# Connectors.net
KiCad netlist of a schematic drawn in Altium Designer
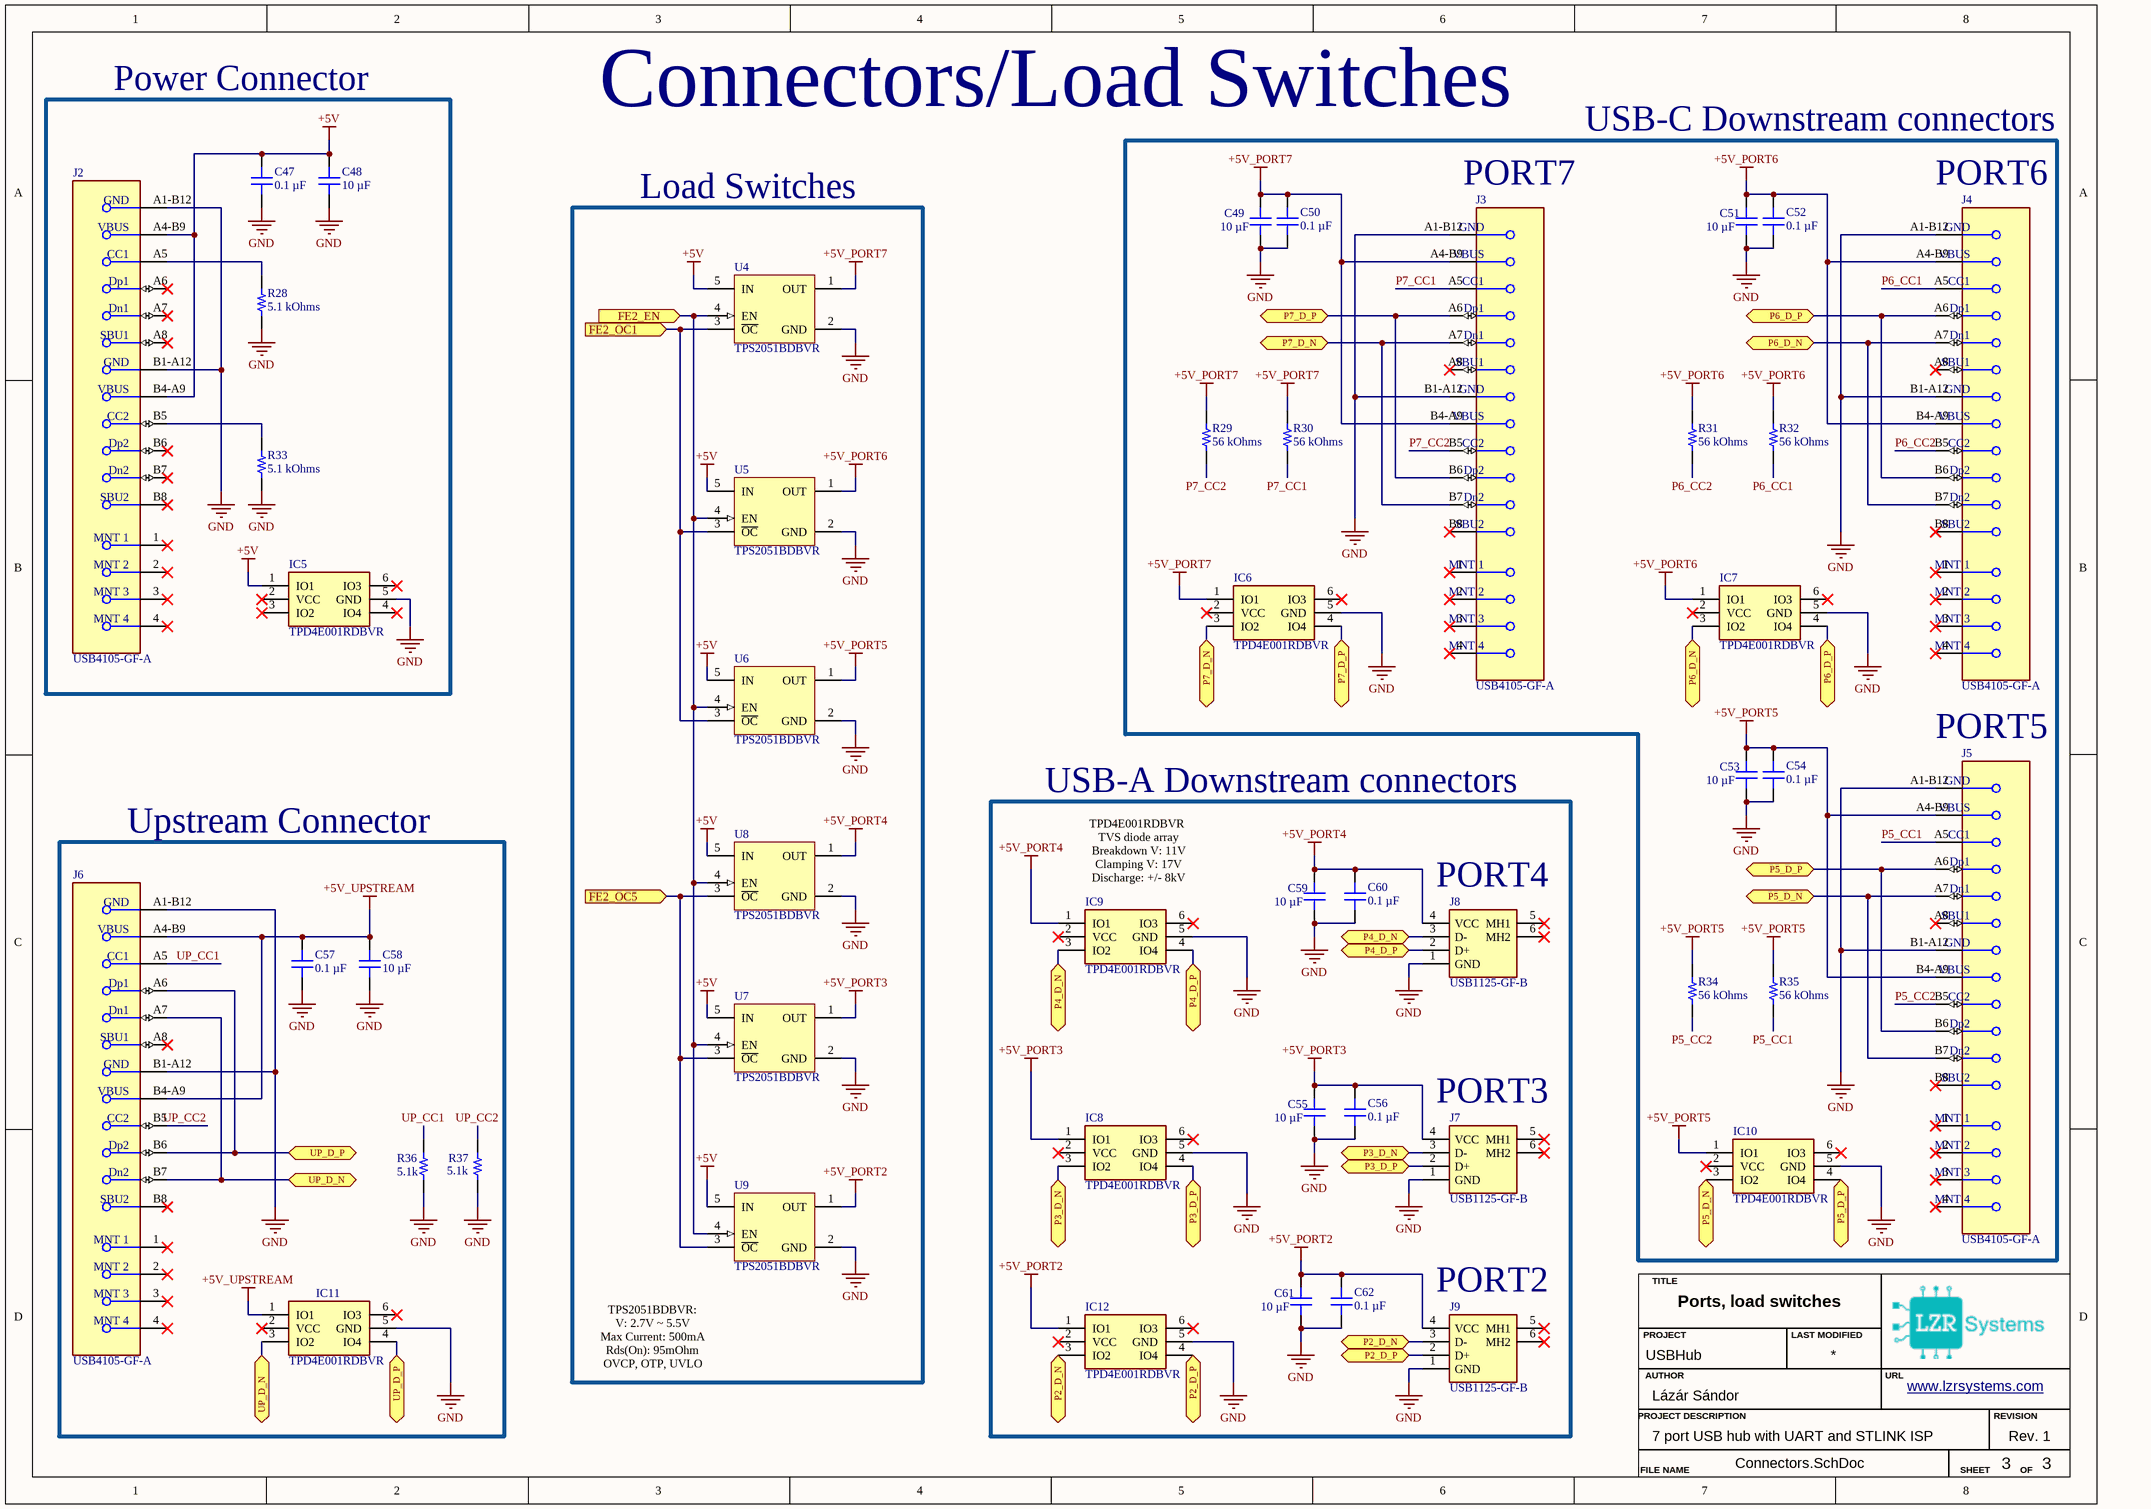
[diagram p0: Connectors.SchDoc]

(export (version "E")
  (design (tool "Eeschema 10.0.6"))
  (components
    (comp (ref "C47")
      (value "0.1 µF")
      (footprint "CAP 0603_1608")
      (description "CAP CER 0.1UF 50V X7R 0603")
      (fields
        (field (name "PART NUMBER") "GCJ188R71H104KA12D")
        (field (name "CAPACITANCE") "0.1 µF")
        (field (name "MANUFACTURER") "Murata Electronics")
      )
      (libsource (lib "Celestial Altium Library - altium_library") (part "Capacitor"))
    )
    (comp (ref "C48")
      (value "10 µF")
      (footprint "MURATA GRM21B 0805_2012")
      (description "CAP CER 10UF 25V X5R 0805")
      (fields
        (field (name "PART NUMBER") "GRM21BR61E106KA73K")
        (field (name "CAPACITANCE") "10 µF")
        (field (name "MANUFACTURER") "Murata Electronics")
      )
      (libsource (lib "Celestial Altium Library - altium_library") (part "Capacitor"))
    )
    (comp (ref "C49")
      (value "10 µF")
      (footprint "MURATA GRM21B 0805_2012")
      (description "CAP CER 10UF 25V X5R 0805")
      (fields
        (field (name "PART NUMBER") "GRM21BR61E106KA73K")
        (field (name "CAPACITANCE") "10 µF")
        (field (name "MANUFACTURER") "Murata Electronics")
      )
      (libsource (lib "Celestial Altium Library - altium_library") (part "Capacitor"))
    )
    (comp (ref "C50")
      (value "0.1 µF")
      (footprint "CAP 0603_1608")
      (description "CAP CER 0.1UF 50V X7R 0603")
      (fields
        (field (name "PART NUMBER") "GCJ188R71H104KA12D")
        (field (name "CAPACITANCE") "0.1 µF")
        (field (name "MANUFACTURER") "Murata Electronics")
      )
      (libsource (lib "Celestial Altium Library - altium_library") (part "Capacitor"))
    )
    (comp (ref "C51")
      (value "10 µF")
      (footprint "MURATA GRM21B 0805_2012")
      (description "CAP CER 10UF 25V X5R 0805")
      (fields
        (field (name "PART NUMBER") "GRM21BR61E106KA73K")
        (field (name "CAPACITANCE") "10 µF")
        (field (name "MANUFACTURER") "Murata Electronics")
      )
      (libsource (lib "Celestial Altium Library - altium_library") (part "Capacitor"))
    )
    (comp (ref "C52")
      (value "0.1 µF")
      (footprint "CAP 0603_1608")
      (description "CAP CER 0.1UF 50V X7R 0603")
      (fields
        (field (name "PART NUMBER") "GCJ188R71H104KA12D")
        (field (name "CAPACITANCE") "0.1 µF")
        (field (name "MANUFACTURER") "Murata Electronics")
      )
      (libsource (lib "Celestial Altium Library - altium_library") (part "Capacitor"))
    )
    (comp (ref "C53")
      (value "10 µF")
      (footprint "MURATA GRM21B 0805_2012")
      (description "CAP CER 10UF 25V X5R 0805")
      (fields
        (field (name "PART NUMBER") "GRM21BR61E106KA73K")
        (field (name "CAPACITANCE") "10 µF")
        (field (name "MANUFACTURER") "Murata Electronics")
      )
      (libsource (lib "Celestial Altium Library - altium_library") (part "Capacitor"))
    )
    (comp (ref "C54")
      (value "0.1 µF")
      (footprint "CAP 0603_1608")
      (description "CAP CER 0.1UF 50V X7R 0603")
      (fields
        (field (name "PART NUMBER") "GCJ188R71H104KA12D")
        (field (name "CAPACITANCE") "0.1 µF")
        (field (name "MANUFACTURER") "Murata Electronics")
      )
      (libsource (lib "Celestial Altium Library - altium_library") (part "Capacitor"))
    )
    (comp (ref "C55")
      (value "10 µF")
      (footprint "MURATA GRM21B 0805_2012")
      (description "CAP CER 10UF 25V X5R 0805")
      (fields
        (field (name "PART NUMBER") "GRM21BR61E106KA73K")
        (field (name "CAPACITANCE") "10 µF")
        (field (name "MANUFACTURER") "Murata Electronics")
      )
      (libsource (lib "Celestial Altium Library - altium_library") (part "Capacitor"))
    )
    (comp (ref "C56")
      (value "0.1 µF")
      (footprint "CAP 0603_1608")
      (description "CAP CER 0.1UF 50V X7R 0603")
      (fields
        (field (name "PART NUMBER") "GCJ188R71H104KA12D")
        (field (name "CAPACITANCE") "0.1 µF")
        (field (name "MANUFACTURER") "Murata Electronics")
      )
      (libsource (lib "Celestial Altium Library - altium_library") (part "Capacitor"))
    )
    (comp (ref "C57")
      (value "0.1 µF")
      (footprint "CAP 0603_1608")
      (description "CAP CER 0.1UF 50V X7R 0603")
      (fields
        (field (name "PART NUMBER") "GCJ188R71H104KA12D")
        (field (name "CAPACITANCE") "0.1 µF")
        (field (name "MANUFACTURER") "Murata Electronics")
      )
      (libsource (lib "Celestial Altium Library - altium_library") (part "Capacitor"))
    )
    (comp (ref "C58")
      (value "10 µF")
      (footprint "MURATA GRM21B 0805_2012")
      (description "CAP CER 10UF 25V X5R 0805")
      (fields
        (field (name "PART NUMBER") "GRM21BR61E106KA73K")
        (field (name "CAPACITANCE") "10 µF")
        (field (name "MANUFACTURER") "Murata Electronics")
      )
      (libsource (lib "Celestial Altium Library - altium_library") (part "Capacitor"))
    )
    (comp (ref "C59")
      (value "10 µF")
      (footprint "MURATA GRM21B 0805_2012")
      (description "CAP CER 10UF 25V X5R 0805")
      (fields
        (field (name "PART NUMBER") "GRM21BR61E106KA73K")
        (field (name "CAPACITANCE") "10 µF")
        (field (name "MANUFACTURER") "Murata Electronics")
      )
      (libsource (lib "Celestial Altium Library - altium_library") (part "Capacitor"))
    )
    (comp (ref "C60")
      (value "0.1 µF")
      (footprint "CAP 0603_1608")
      (description "CAP CER 0.1UF 50V X7R 0603")
      (fields
        (field (name "PART NUMBER") "GCJ188R71H104KA12D")
        (field (name "CAPACITANCE") "0.1 µF")
        (field (name "MANUFACTURER") "Murata Electronics")
      )
      (libsource (lib "Celestial Altium Library - altium_library") (part "Capacitor"))
    )
    (comp (ref "C61")
      (value "10 µF")
      (footprint "MURATA GRM21B 0805_2012")
      (description "CAP CER 10UF 25V X5R 0805")
      (fields
        (field (name "PART NUMBER") "GRM21BR61E106KA73K")
        (field (name "CAPACITANCE") "10 µF")
        (field (name "MANUFACTURER") "Murata Electronics")
      )
      (libsource (lib "Celestial Altium Library - altium_library") (part "Capacitor"))
    )
    (comp (ref "C62")
      (value "0.1 µF")
      (footprint "CAP 0603_1608")
      (description "CAP CER 0.1UF 50V X7R 0603")
      (fields
        (field (name "PART NUMBER") "GCJ188R71H104KA12D")
        (field (name "CAPACITANCE") "0.1 µF")
        (field (name "MANUFACTURER") "Murata Electronics")
      )
      (libsource (lib "Celestial Altium Library - altium_library") (part "Capacitor"))
    )
    (comp (ref "IC5")
      (value "TPD4E001RDBVR")
      (footprint "SamacSys:SOT95P280X145-6N")
      (description "Integrated Circuit")
      (fields (field (name "MOUSER PART NUMBER") "595-TPD4E001RDBVR"))
      (libsource (lib "*") (part "TPD4E001RDBVR"))
    )
    (comp (ref "IC6")
      (value "TPD4E001RDBVR")
      (footprint "SamacSys:SOT95P280X145-6N")
      (description "Integrated Circuit")
      (fields (field (name "MOUSER PART NUMBER") "595-TPD4E001RDBVR"))
      (libsource (lib "*") (part "TPD4E001RDBVR"))
    )
    (comp (ref "IC7")
      (value "TPD4E001RDBVR")
      (footprint "SamacSys:SOT95P280X145-6N")
      (description "Integrated Circuit")
      (fields (field (name "MOUSER PART NUMBER") "595-TPD4E001RDBVR"))
      (libsource (lib "*") (part "TPD4E001RDBVR"))
    )
    (comp (ref "IC8")
      (value "TPD4E001RDBVR")
      (footprint "SamacSys:SOT95P280X145-6N")
      (description "Integrated Circuit")
      (fields (field (name "MOUSER PART NUMBER") "595-TPD4E001RDBVR"))
      (libsource (lib "*") (part "TPD4E001RDBVR"))
    )
    (comp (ref "IC9")
      (value "TPD4E001RDBVR")
      (footprint "SamacSys:SOT95P280X145-6N")
      (description "Integrated Circuit")
      (fields (field (name "MOUSER PART NUMBER") "595-TPD4E001RDBVR"))
      (libsource (lib "*") (part "TPD4E001RDBVR"))
    )
    (comp (ref "IC10")
      (value "TPD4E001RDBVR")
      (footprint "SamacSys:SOT95P280X145-6N")
      (description "Integrated Circuit")
      (fields (field (name "MOUSER PART NUMBER") "595-TPD4E001RDBVR"))
      (libsource (lib "*") (part "TPD4E001RDBVR"))
    )
    (comp (ref "IC11")
      (value "TPD4E001RDBVR")
      (footprint "SamacSys:SOT95P280X145-6N")
      (description "Integrated Circuit")
      (fields (field (name "MOUSER PART NUMBER") "595-TPD4E001RDBVR"))
      (libsource (lib "*") (part "TPD4E001RDBVR"))
    )
    (comp (ref "IC12")
      (value "TPD4E001RDBVR")
      (footprint "SamacSys:SOT95P280X145-6N")
      (description "Integrated Circuit")
      (fields (field (name "MOUSER PART NUMBER") "595-TPD4E001RDBVR"))
      (libsource (lib "*") (part "TPD4E001RDBVR"))
    )
    (comp (ref "J2")
      (value "USB4105-GF-A")
      (footprint "FP-USB4105-GF-A-MFG")
      (description "Conn USB 2.0 Type C RCP 24 POS 0.3mm/0.5mm Solder RA SMD 24 Terminal 1 Port T/R")
      (libsource (lib "") (part "e7c17a616881a82b79941196b4bec10_1"))
    )
    (comp (ref "J3")
      (value "USB4105-GF-A")
      (footprint "FP-USB4105-GF-A-MFG")
      (description "Conn USB 2.0 Type C RCP 24 POS 0.3mm/0.5mm Solder RA SMD 24 Terminal 1 Port T/R")
      (libsource (lib "Sandor Lazar") (part "e7c17a616881a82b79941196b4bec10"))
    )
    (comp (ref "J4")
      (value "USB4105-GF-A")
      (footprint "FP-USB4105-GF-A-MFG")
      (description "Conn USB 2.0 Type C RCP 24 POS 0.3mm/0.5mm Solder RA SMD 24 Terminal 1 Port T/R")
      (libsource (lib "Sandor Lazar") (part "e7c17a616881a82b79941196b4bec10"))
    )
    (comp (ref "J5")
      (value "USB4105-GF-A")
      (footprint "FP-USB4105-GF-A-MFG")
      (description "Conn USB 2.0 Type C RCP 24 POS 0.3mm/0.5mm Solder RA SMD 24 Terminal 1 Port T/R")
      (libsource (lib "Sandor Lazar") (part "e7c17a616881a82b79941196b4bec10"))
    )
    (comp (ref "J6")
      (value "USB4105-GF-A")
      (footprint "FP-USB4105-GF-A-MFG")
      (description "Conn USB 2.0 Type C RCP 24 POS 0.3mm/0.5mm Solder RA SMD 24 Terminal 1 Port T/R")
      (libsource (lib "") (part "e7c17a616881a82b79941196b4bec10_1"))
    )
    (comp (ref "J7")
      (value "USB1125-GF-B")
      (footprint "SamacSys:USB1125GFB")
      (description "Connector")
      (fields (field (name "MOUSER PART NUMBER") "640-USB1125-GF-B"))
      (libsource (lib "SamacSys") (part "USB1125-GF-B"))
    )
    (comp (ref "J8")
      (value "USB1125-GF-B")
      (footprint "SamacSys:USB1125GFB")
      (description "Connector")
      (fields (field (name "MOUSER PART NUMBER") "640-USB1125-GF-B"))
      (libsource (lib "SamacSys") (part "USB1125-GF-B"))
    )
    (comp (ref "J9")
      (value "USB1125-GF-B")
      (footprint "SamacSys:USB1125GFB")
      (description "Connector")
      (fields (field (name "MOUSER PART NUMBER") "640-USB1125-GF-B"))
      (libsource (lib "SamacSys") (part "USB1125-GF-B"))
    )
    (comp (ref "R28")
      (value "5.1 kOhms")
      (footprint "KOA RES RK73 RN73 0603_1608")
      (description "RESISTOR")
      (fields
        (field (name "PART NUMBER") "RK73B1JTTDD512J")
        (field (name "MANUFACTURER") "KOA Speer Electronics, Inc.")
      )
      (libsource (lib "Celestial Altium Library - altium_library") (part "Resistor"))
    )
    (comp (ref "R29")
      (value "56 kOhms")
      (footprint "YAGEO RES 0603_1608")
      (description "RES 56K OHM 5% 1/10W 0603")
      (fields (field (name "PART NUMBER") "RC0603JR-0756KL") (field (name "MANUFACTURER") "Yageo"))
      (libsource (lib "Celestial Altium Library - altium_library") (part "Resistor"))
    )
    (comp (ref "R30")
      (value "56 kOhms")
      (footprint "YAGEO RES 0603_1608")
      (description "RES 56K OHM 5% 1/10W 0603")
      (fields (field (name "PART NUMBER") "RC0603JR-0756KL") (field (name "MANUFACTURER") "Yageo"))
      (libsource (lib "Celestial Altium Library - altium_library") (part "Resistor"))
    )
    (comp (ref "R31")
      (value "56 kOhms")
      (footprint "YAGEO RES 0603_1608")
      (description "RES 56K OHM 5% 1/10W 0603")
      (fields (field (name "PART NUMBER") "RC0603JR-0756KL") (field (name "MANUFACTURER") "Yageo"))
      (libsource (lib "Celestial Altium Library - altium_library") (part "Resistor"))
    )
    (comp (ref "R32")
      (value "56 kOhms")
      (footprint "YAGEO RES 0603_1608")
      (description "RES 56K OHM 5% 1/10W 0603")
      (fields (field (name "PART NUMBER") "RC0603JR-0756KL") (field (name "MANUFACTURER") "Yageo"))
      (libsource (lib "Celestial Altium Library - altium_library") (part "Resistor"))
    )
    (comp (ref "R33")
      (value "5.1 kOhms")
      (footprint "KOA RES RK73 RN73 0603_1608")
      (description "RESISTOR")
      (fields
        (field (name "PART NUMBER") "RK73B1JTTDD512J")
        (field (name "MANUFACTURER") "KOA Speer Electronics, Inc.")
      )
      (libsource (lib "Celestial Altium Library - altium_library") (part "Resistor"))
    )
    (comp (ref "R34")
      (value "56 kOhms")
      (footprint "YAGEO RES 0603_1608")
      (description "RES 56K OHM 5% 1/10W 0603")
      (fields (field (name "PART NUMBER") "RC0603JR-0756KL") (field (name "MANUFACTURER") "Yageo"))
      (libsource (lib "Celestial Altium Library - altium_library") (part "Resistor"))
    )
    (comp (ref "R35")
      (value "56 kOhms")
      (footprint "YAGEO RES 0603_1608")
      (description "RES 56K OHM 5% 1/10W 0603")
      (fields (field (name "PART NUMBER") "RC0603JR-0756KL") (field (name "MANUFACTURER") "Yageo"))
      (libsource (lib "Celestial Altium Library - altium_library") (part "Resistor"))
    )
    (comp (ref "R36")
      (value "5.1k")
      (footprint "KOA RES RK73 RN73 0603_1608")
      (description "RESISTOR")
      (fields
        (field (name "PART NUMBER") "RK73B1JTTDD512J")
        (field (name "MANUFACTURER") "KOA Speer Electronics, Inc.")
      )
      (libsource (lib "Celestial Altium Library - altium_library") (part "Resistor"))
    )
    (comp (ref "R37")
      (value "5.1k")
      (footprint "KOA RES RK73 RN73 0603_1608")
      (description "RESISTOR")
      (fields
        (field (name "PART NUMBER") "RK73B1JTTDD512J")
        (field (name "MANUFACTURER") "KOA Speer Electronics, Inc.")
      )
      (libsource (lib "Celestial Altium Library - altium_library") (part "Resistor"))
    )
    (comp (ref "U4")
      (value "TPS2051BDBVR")
      (footprint "DBV0005A_L")
      (description "0.5A loading, 2.7-5.5V, 70mΩ USB power switch, active-high 5-SOT-23 -40 to 125")
      (libsource (lib "Sandor Lazar") (part "TI-TPS2051BDBV5"))
    )
    (comp (ref "U5")
      (value "TPS2051BDBVR")
      (footprint "DBV0005A_L")
      (description "0.5A loading, 2.7-5.5V, 70mΩ USB power switch, active-high 5-SOT-23 -40 to 125")
      (libsource (lib "Sandor Lazar") (part "TI-TPS2051BDBV5"))
    )
    (comp (ref "U6")
      (value "TPS2051BDBVR")
      (footprint "DBV0005A_L")
      (description "0.5A loading, 2.7-5.5V, 70mΩ USB power switch, active-high 5-SOT-23 -40 to 125")
      (libsource (lib "Sandor Lazar") (part "TI-TPS2051BDBV5"))
    )
    (comp (ref "U7")
      (value "TPS2051BDBVR")
      (footprint "DBV0005A_L")
      (description "0.5A loading, 2.7-5.5V, 70mΩ USB power switch, active-high 5-SOT-23 -40 to 125")
      (libsource (lib "Sandor Lazar") (part "TI-TPS2051BDBV5"))
    )
    (comp (ref "U8")
      (value "TPS2051BDBVR")
      (footprint "DBV0005A_L")
      (description "0.5A loading, 2.7-5.5V, 70mΩ USB power switch, active-high 5-SOT-23 -40 to 125")
      (libsource (lib "Sandor Lazar") (part "TI-TPS2051BDBV5"))
    )
    (comp (ref "U9")
      (value "TPS2051BDBVR")
      (footprint "DBV0005A_L")
      (description "0.5A loading, 2.7-5.5V, 70mΩ USB power switch, active-high 5-SOT-23 -40 to 125")
      (libsource (lib "Sandor Lazar") (part "TI-TPS2051BDBV5"))
    )
  )
  (nets
    (net (code "1") (name "+5V") (class "Default")
      (node (ref "C47") (pin "2") (pinfunction "2_2") (pintype "passive"))
      (node (ref "C48") (pin "2") (pinfunction "2_2") (pintype "passive"))
      (node (ref "IC5") (pin "1") (pinfunction "IO1_1") (pintype "passive"))
      (node (ref "J2") (pin "A4-B9") (pinfunction "VBUS_A4-B9") (pintype "power_in"))
      (node (ref "J2") (pin "B4-A9") (pinfunction "VBUS_B4-A9") (pintype "power_in"))
      (node (ref "U4") (pin "5") (pinfunction "IN_5") (pintype "power_in"))
      (node (ref "U5") (pin "5") (pinfunction "IN_5") (pintype "power_in"))
      (node (ref "U6") (pin "5") (pinfunction "IN_5") (pintype "power_in"))
      (node (ref "U7") (pin "5") (pinfunction "IN_5") (pintype "power_in"))
      (node (ref "U8") (pin "5") (pinfunction "IN_5") (pintype "power_in"))
      (node (ref "U9") (pin "5") (pinfunction "IN_5") (pintype "power_in"))
    )
    (net (code "2") (name "+5V_PORT2") (class "Default")
      (node (ref "C61") (pin "2") (pinfunction "2_2") (pintype "passive"))
      (node (ref "C62") (pin "2") (pinfunction "2_2") (pintype "passive"))
      (node (ref "IC12") (pin "1") (pinfunction "IO1_1") (pintype "passive"))
      (node (ref "J9") (pin "4") (pinfunction "VCC_4") (pintype "passive"))
      (node (ref "U9") (pin "1") (pinfunction "OUT_1") (pintype "power_in"))
    )
    (net (code "3") (name "+5V_PORT3") (class "Default")
      (node (ref "C55") (pin "2") (pinfunction "2_2") (pintype "passive"))
      (node (ref "C56") (pin "2") (pinfunction "2_2") (pintype "passive"))
      (node (ref "IC8") (pin "1") (pinfunction "IO1_1") (pintype "passive"))
      (node (ref "J7") (pin "4") (pinfunction "VCC_4") (pintype "passive"))
      (node (ref "U7") (pin "1") (pinfunction "OUT_1") (pintype "power_in"))
    )
    (net (code "4") (name "+5V_PORT4") (class "Default")
      (node (ref "C59") (pin "2") (pinfunction "2_2") (pintype "passive"))
      (node (ref "C60") (pin "2") (pinfunction "2_2") (pintype "passive"))
      (node (ref "IC9") (pin "1") (pinfunction "IO1_1") (pintype "passive"))
      (node (ref "J8") (pin "4") (pinfunction "VCC_4") (pintype "passive"))
      (node (ref "U8") (pin "1") (pinfunction "OUT_1") (pintype "power_in"))
    )
    (net (code "5") (name "+5V_PORT5") (class "Default")
      (node (ref "C53") (pin "2") (pinfunction "2_2") (pintype "passive"))
      (node (ref "C54") (pin "2") (pinfunction "2_2") (pintype "passive"))
      (node (ref "IC10") (pin "1") (pinfunction "IO1_1") (pintype "passive"))
      (node (ref "J5") (pin "A4-B9") (pinfunction "VBUS_A4-B9") (pintype "power_in"))
      (node (ref "J5") (pin "B4-A9") (pinfunction "VBUS_B4-A9") (pintype "power_in"))
      (node (ref "R34") (pin "2") (pinfunction "2_2") (pintype "passive"))
      (node (ref "R35") (pin "2") (pinfunction "2_2") (pintype "passive"))
      (node (ref "U6") (pin "1") (pinfunction "OUT_1") (pintype "power_in"))
    )
    (net (code "6") (name "+5V_PORT6") (class "Default")
      (node (ref "C51") (pin "2") (pinfunction "2_2") (pintype "passive"))
      (node (ref "C52") (pin "2") (pinfunction "2_2") (pintype "passive"))
      (node (ref "IC7") (pin "1") (pinfunction "IO1_1") (pintype "passive"))
      (node (ref "J4") (pin "A4-B9") (pinfunction "VBUS_A4-B9") (pintype "power_in"))
      (node (ref "J4") (pin "B4-A9") (pinfunction "VBUS_B4-A9") (pintype "power_in"))
      (node (ref "R31") (pin "2") (pinfunction "2_2") (pintype "passive"))
      (node (ref "R32") (pin "2") (pinfunction "2_2") (pintype "passive"))
      (node (ref "U5") (pin "1") (pinfunction "OUT_1") (pintype "power_in"))
    )
    (net (code "7") (name "+5V_PORT7") (class "Default")
      (node (ref "C49") (pin "2") (pinfunction "2_2") (pintype "passive"))
      (node (ref "C50") (pin "2") (pinfunction "2_2") (pintype "passive"))
      (node (ref "IC6") (pin "1") (pinfunction "IO1_1") (pintype "passive"))
      (node (ref "J3") (pin "A4-B9") (pinfunction "VBUS_A4-B9") (pintype "power_in"))
      (node (ref "J3") (pin "B4-A9") (pinfunction "VBUS_B4-A9") (pintype "power_in"))
      (node (ref "R29") (pin "2") (pinfunction "2_2") (pintype "passive"))
      (node (ref "R30") (pin "2") (pinfunction "2_2") (pintype "passive"))
      (node (ref "U4") (pin "1") (pinfunction "OUT_1") (pintype "power_in"))
    )
    (net (code "8") (name "+5V_UPSTREAM") (class "Default")
      (node (ref "C57") (pin "2") (pinfunction "2_2") (pintype "passive"))
      (node (ref "C58") (pin "2") (pinfunction "2_2") (pintype "passive"))
      (node (ref "IC11") (pin "1") (pinfunction "IO1_1") (pintype "passive"))
      (node (ref "J6") (pin "A4-B9") (pinfunction "VBUS_A4-B9") (pintype "power_in"))
      (node (ref "J6") (pin "B4-A9") (pinfunction "VBUS_B4-A9") (pintype "power_in"))
    )
    (net (code "9") (name "/FE2_EN") (class "Default")
      (node (ref "U4") (pin "4") (pinfunction "EN_4") (pintype "input"))
      (node (ref "U5") (pin "4") (pinfunction "EN_4") (pintype "input"))
      (node (ref "U6") (pin "4") (pinfunction "EN_4") (pintype "input"))
      (node (ref "U7") (pin "4") (pinfunction "EN_4") (pintype "input"))
      (node (ref "U8") (pin "4") (pinfunction "EN_4") (pintype "input"))
      (node (ref "U9") (pin "4") (pinfunction "EN_4") (pintype "input"))
    )
    (net (code "10") (name "/FE2_OC1") (class "Default")
      (node (ref "U4") (pin "3") (pinfunction "~{OC}_3") (pintype "passive"))
      (node (ref "U5") (pin "3") (pinfunction "~{OC}_3") (pintype "passive"))
      (node (ref "U6") (pin "3") (pinfunction "~{OC}_3") (pintype "passive"))
    )
    (net (code "11") (name "/FE2_OC5") (class "Default")
      (node (ref "U7") (pin "3") (pinfunction "~{OC}_3") (pintype "passive"))
      (node (ref "U8") (pin "3") (pinfunction "~{OC}_3") (pintype "passive"))
      (node (ref "U9") (pin "3") (pinfunction "~{OC}_3") (pintype "passive"))
    )
    (net (code "12") (name "/P2_D_N") (class "Default")
      (node (ref "IC12") (pin "3") (pinfunction "IO2_3") (pintype "passive"))
      (node (ref "J9") (pin "3") (pinfunction "D-_3") (pintype "passive"))
    )
    (net (code "13") (name "/P2_D_P") (class "Default")
      (node (ref "IC12") (pin "4") (pinfunction "IO4_4") (pintype "passive"))
      (node (ref "J9") (pin "2") (pinfunction "D+_2") (pintype "passive"))
    )
    (net (code "14") (name "/P3_D_N") (class "Default")
      (node (ref "IC8") (pin "3") (pinfunction "IO2_3") (pintype "passive"))
      (node (ref "J7") (pin "3") (pinfunction "D-_3") (pintype "passive"))
    )
    (net (code "15") (name "/P3_D_P") (class "Default")
      (node (ref "IC8") (pin "4") (pinfunction "IO4_4") (pintype "passive"))
      (node (ref "J7") (pin "2") (pinfunction "D+_2") (pintype "passive"))
    )
    (net (code "16") (name "/P4_D_N") (class "Default")
      (node (ref "IC9") (pin "3") (pinfunction "IO2_3") (pintype "passive"))
      (node (ref "J8") (pin "3") (pinfunction "D-_3") (pintype "passive"))
    )
    (net (code "17") (name "/P4_D_P") (class "Default")
      (node (ref "IC9") (pin "4") (pinfunction "IO4_4") (pintype "passive"))
      (node (ref "J8") (pin "2") (pinfunction "D+_2") (pintype "passive"))
    )
    (net (code "18") (name "/P5_CC1") (class "Default")
      (node (ref "J5") (pin "A5") (pinfunction "CC1_A5") (pintype "power_in"))
      (node (ref "R35") (pin "1") (pinfunction "1_1") (pintype "passive"))
    )
    (net (code "19") (name "/P5_CC2") (class "Default")
      (node (ref "J5") (pin "B5") (pinfunction "CC2_B5") (pintype "bidirectional"))
      (node (ref "R34") (pin "1") (pinfunction "1_1") (pintype "passive"))
    )
    (net (code "20") (name "/P5_D_N") (class "Default")
      (node (ref "IC10") (pin "3") (pinfunction "IO2_3") (pintype "passive"))
      (node (ref "J5") (pin "A7") (pinfunction "Dn1_A7") (pintype "bidirectional"))
      (node (ref "J5") (pin "B7") (pinfunction "Dn2_B7") (pintype "bidirectional"))
    )
    (net (code "21") (name "/P5_D_P") (class "Default")
      (node (ref "IC10") (pin "4") (pinfunction "IO4_4") (pintype "passive"))
      (node (ref "J5") (pin "A6") (pinfunction "Dp1_A6") (pintype "bidirectional"))
      (node (ref "J5") (pin "B6") (pinfunction "Dp2_B6") (pintype "bidirectional"))
    )
    (net (code "22") (name "/P6_CC1") (class "Default")
      (node (ref "J4") (pin "A5") (pinfunction "CC1_A5") (pintype "power_in"))
      (node (ref "R32") (pin "1") (pinfunction "1_1") (pintype "passive"))
    )
    (net (code "23") (name "/P6_CC2") (class "Default")
      (node (ref "J4") (pin "B5") (pinfunction "CC2_B5") (pintype "bidirectional"))
      (node (ref "R31") (pin "1") (pinfunction "1_1") (pintype "passive"))
    )
    (net (code "24") (name "/P6_D_N") (class "Default")
      (node (ref "IC7") (pin "3") (pinfunction "IO2_3") (pintype "passive"))
      (node (ref "J4") (pin "A7") (pinfunction "Dn1_A7") (pintype "bidirectional"))
      (node (ref "J4") (pin "B7") (pinfunction "Dn2_B7") (pintype "bidirectional"))
    )
    (net (code "25") (name "/P6_D_P") (class "Default")
      (node (ref "IC7") (pin "4") (pinfunction "IO4_4") (pintype "passive"))
      (node (ref "J4") (pin "A6") (pinfunction "Dp1_A6") (pintype "bidirectional"))
      (node (ref "J4") (pin "B6") (pinfunction "Dp2_B6") (pintype "bidirectional"))
    )
    (net (code "26") (name "/P7_CC1") (class "Default")
      (node (ref "J3") (pin "A5") (pinfunction "CC1_A5") (pintype "power_in"))
      (node (ref "R30") (pin "1") (pinfunction "1_1") (pintype "passive"))
    )
    (net (code "27") (name "/P7_CC2") (class "Default")
      (node (ref "J3") (pin "B5") (pinfunction "CC2_B5") (pintype "bidirectional"))
      (node (ref "R29") (pin "1") (pinfunction "1_1") (pintype "passive"))
    )
    (net (code "28") (name "/P7_D_N") (class "Default")
      (node (ref "IC6") (pin "3") (pinfunction "IO2_3") (pintype "passive"))
      (node (ref "J3") (pin "A7") (pinfunction "Dn1_A7") (pintype "bidirectional"))
      (node (ref "J3") (pin "B7") (pinfunction "Dn2_B7") (pintype "bidirectional"))
    )
    (net (code "29") (name "/P7_D_P") (class "Default")
      (node (ref "IC6") (pin "4") (pinfunction "IO4_4") (pintype "passive"))
      (node (ref "J3") (pin "A6") (pinfunction "Dp1_A6") (pintype "bidirectional"))
      (node (ref "J3") (pin "B6") (pinfunction "Dp2_B6") (pintype "bidirectional"))
    )
    (net (code "30") (name "/UP_CC1") (class "Default")
      (node (ref "J6") (pin "A5") (pinfunction "CC1_A5") (pintype "power_in"))
      (node (ref "R36") (pin "2") (pinfunction "2_2") (pintype "passive"))
    )
    (net (code "31") (name "/UP_CC2") (class "Default")
      (node (ref "J6") (pin "B5") (pinfunction "CC2_B5") (pintype "bidirectional"))
      (node (ref "R37") (pin "2") (pinfunction "2_2") (pintype "passive"))
    )
    (net (code "32") (name "/UP_D_N") (class "Default")
      (node (ref "IC11") (pin "3") (pinfunction "IO2_3") (pintype "passive"))
      (node (ref "J6") (pin "A7") (pinfunction "Dn1_A7") (pintype "bidirectional"))
      (node (ref "J6") (pin "B7") (pinfunction "Dn2_B7") (pintype "bidirectional"))
    )
    (net (code "33") (name "/UP_D_P") (class "Default")
      (node (ref "IC11") (pin "4") (pinfunction "IO4_4") (pintype "passive"))
      (node (ref "J6") (pin "A6") (pinfunction "Dp1_A6") (pintype "bidirectional"))
      (node (ref "J6") (pin "B6") (pinfunction "Dp2_B6") (pintype "bidirectional"))
    )
    (net (code "34") (name "GND") (class "Default")
      (node (ref "C47") (pin "1") (pinfunction "1_1") (pintype "passive"))
      (node (ref "C48") (pin "1") (pinfunction "1_1") (pintype "passive"))
      (node (ref "C49") (pin "1") (pinfunction "1_1") (pintype "passive"))
      (node (ref "C50") (pin "1") (pinfunction "1_1") (pintype "passive"))
      (node (ref "C51") (pin "1") (pinfunction "1_1") (pintype "passive"))
      (node (ref "C52") (pin "1") (pinfunction "1_1") (pintype "passive"))
      (node (ref "C53") (pin "1") (pinfunction "1_1") (pintype "passive"))
      (node (ref "C54") (pin "1") (pinfunction "1_1") (pintype "passive"))
      (node (ref "C55") (pin "1") (pinfunction "1_1") (pintype "passive"))
      (node (ref "C56") (pin "1") (pinfunction "1_1") (pintype "passive"))
      (node (ref "C57") (pin "1") (pinfunction "1_1") (pintype "passive"))
      (node (ref "C58") (pin "1") (pinfunction "1_1") (pintype "passive"))
      (node (ref "C59") (pin "1") (pinfunction "1_1") (pintype "passive"))
      (node (ref "C60") (pin "1") (pinfunction "1_1") (pintype "passive"))
      (node (ref "C61") (pin "1") (pinfunction "1_1") (pintype "passive"))
      (node (ref "C62") (pin "1") (pinfunction "1_1") (pintype "passive"))
      (node (ref "IC10") (pin "5") (pinfunction "GND_5") (pintype "passive"))
      (node (ref "IC11") (pin "5") (pinfunction "GND_5") (pintype "passive"))
      (node (ref "IC12") (pin "5") (pinfunction "GND_5") (pintype "passive"))
      (node (ref "IC5") (pin "5") (pinfunction "GND_5") (pintype "passive"))
      (node (ref "IC6") (pin "5") (pinfunction "GND_5") (pintype "passive"))
      (node (ref "IC7") (pin "5") (pinfunction "GND_5") (pintype "passive"))
      (node (ref "IC8") (pin "5") (pinfunction "GND_5") (pintype "passive"))
      (node (ref "IC9") (pin "5") (pinfunction "GND_5") (pintype "passive"))
      (node (ref "J2") (pin "A1-B12") (pinfunction "GND_A1-B12") (pintype "power_in"))
      (node (ref "J2") (pin "B1-A12") (pinfunction "GND_B1-A12") (pintype "power_in"))
      (node (ref "J3") (pin "A1-B12") (pinfunction "GND_A1-B12") (pintype "power_in"))
      (node (ref "J3") (pin "B1-A12") (pinfunction "GND_B1-A12") (pintype "power_in"))
      (node (ref "J4") (pin "A1-B12") (pinfunction "GND_A1-B12") (pintype "power_in"))
      (node (ref "J4") (pin "B1-A12") (pinfunction "GND_B1-A12") (pintype "power_in"))
      (node (ref "J5") (pin "A1-B12") (pinfunction "GND_A1-B12") (pintype "power_in"))
      (node (ref "J5") (pin "B1-A12") (pinfunction "GND_B1-A12") (pintype "power_in"))
      (node (ref "J6") (pin "A1-B12") (pinfunction "GND_A1-B12") (pintype "power_in"))
      (node (ref "J6") (pin "B1-A12") (pinfunction "GND_B1-A12") (pintype "power_in"))
      (node (ref "J7") (pin "1") (pinfunction "GND_1") (pintype "passive"))
      (node (ref "J8") (pin "1") (pinfunction "GND_1") (pintype "passive"))
      (node (ref "J9") (pin "1") (pinfunction "GND_1") (pintype "passive"))
      (node (ref "R28") (pin "1") (pinfunction "1_1") (pintype "passive"))
      (node (ref "R33") (pin "1") (pinfunction "1_1") (pintype "passive"))
      (node (ref "R36") (pin "1") (pinfunction "1_1") (pintype "passive"))
      (node (ref "R37") (pin "1") (pinfunction "1_1") (pintype "passive"))
      (node (ref "U4") (pin "2") (pinfunction "GND_2") (pintype "power_in"))
      (node (ref "U5") (pin "2") (pinfunction "GND_2") (pintype "power_in"))
      (node (ref "U6") (pin "2") (pinfunction "GND_2") (pintype "power_in"))
      (node (ref "U7") (pin "2") (pinfunction "GND_2") (pintype "power_in"))
      (node (ref "U8") (pin "2") (pinfunction "GND_2") (pintype "power_in"))
      (node (ref "U9") (pin "2") (pinfunction "GND_2") (pintype "power_in"))
    )
    (net (code "35") (name "Net-(J2-CC1)") (class "Default")
      (node (ref "J2") (pin "A5") (pinfunction "CC1_A5") (pintype "power_in"))
      (node (ref "R28") (pin "2") (pinfunction "2_2") (pintype "passive"))
    )
    (net (code "36") (name "Net-(J2-CC2)") (class "Default")
      (node (ref "J2") (pin "B5") (pinfunction "CC2_B5") (pintype "bidirectional"))
      (node (ref "R33") (pin "2") (pinfunction "2_2") (pintype "passive"))
    )
    (net (code "37") (name "unconnected-(IC5-IO2-Pad3)") (class "Default")
      (node (ref "IC5") (pin "3") (pinfunction "IO2_3") (pintype "passive+no_connect"))
    )
    (net (code "38") (name "unconnected-(IC5-IO3-Pad6)") (class "Default")
      (node (ref "IC5") (pin "6") (pinfunction "IO3_6") (pintype "passive+no_connect"))
    )
    (net (code "39") (name "unconnected-(IC5-IO4-Pad4)") (class "Default")
      (node (ref "IC5") (pin "4") (pinfunction "IO4_4") (pintype "passive+no_connect"))
    )
    (net (code "40") (name "unconnected-(IC5-VCC-Pad2)") (class "Default")
      (node (ref "IC5") (pin "2") (pinfunction "VCC_2") (pintype "passive+no_connect"))
    )
    (net (code "41") (name "unconnected-(IC6-IO3-Pad6)") (class "Default")
      (node (ref "IC6") (pin "6") (pinfunction "IO3_6") (pintype "passive+no_connect"))
    )
    (net (code "42") (name "unconnected-(IC6-VCC-Pad2)") (class "Default")
      (node (ref "IC6") (pin "2") (pinfunction "VCC_2") (pintype "passive+no_connect"))
    )
    (net (code "43") (name "unconnected-(IC7-IO3-Pad6)") (class "Default")
      (node (ref "IC7") (pin "6") (pinfunction "IO3_6") (pintype "passive+no_connect"))
    )
    (net (code "44") (name "unconnected-(IC7-VCC-Pad2)") (class "Default")
      (node (ref "IC7") (pin "2") (pinfunction "VCC_2") (pintype "passive+no_connect"))
    )
    (net (code "45") (name "unconnected-(IC8-IO3-Pad6)") (class "Default")
      (node (ref "IC8") (pin "6") (pinfunction "IO3_6") (pintype "passive+no_connect"))
    )
    (net (code "46") (name "unconnected-(IC8-VCC-Pad2)") (class "Default")
      (node (ref "IC8") (pin "2") (pinfunction "VCC_2") (pintype "passive+no_connect"))
    )
    (net (code "47") (name "unconnected-(IC9-IO3-Pad6)") (class "Default")
      (node (ref "IC9") (pin "6") (pinfunction "IO3_6") (pintype "passive+no_connect"))
    )
    (net (code "48") (name "unconnected-(IC9-VCC-Pad2)") (class "Default")
      (node (ref "IC9") (pin "2") (pinfunction "VCC_2") (pintype "passive+no_connect"))
    )
    (net (code "49") (name "unconnected-(IC10-IO3-Pad6)") (class "Default")
      (node (ref "IC10") (pin "6") (pinfunction "IO3_6") (pintype "passive+no_connect"))
    )
    (net (code "50") (name "unconnected-(IC10-VCC-Pad2)") (class "Default")
      (node (ref "IC10") (pin "2") (pinfunction "VCC_2") (pintype "passive+no_connect"))
    )
    (net (code "51") (name "unconnected-(IC11-IO3-Pad6)") (class "Default")
      (node (ref "IC11") (pin "6") (pinfunction "IO3_6") (pintype "passive+no_connect"))
    )
    (net (code "52") (name "unconnected-(IC11-VCC-Pad2)") (class "Default")
      (node (ref "IC11") (pin "2") (pinfunction "VCC_2") (pintype "passive+no_connect"))
    )
    (net (code "53") (name "unconnected-(IC12-IO3-Pad6)") (class "Default")
      (node (ref "IC12") (pin "6") (pinfunction "IO3_6") (pintype "passive+no_connect"))
    )
    (net (code "54") (name "unconnected-(IC12-VCC-Pad2)") (class "Default")
      (node (ref "IC12") (pin "2") (pinfunction "VCC_2") (pintype "passive+no_connect"))
    )
    (net (code "55") (name "unconnected-(J2-Dn1-PadA7)") (class "Default")
      (node (ref "J2") (pin "A7") (pinfunction "Dn1_A7") (pintype "bidirectional+no_connect"))
    )
    (net (code "56") (name "unconnected-(J2-Dn2-PadB7)") (class "Default")
      (node (ref "J2") (pin "B7") (pinfunction "Dn2_B7") (pintype "bidirectional+no_connect"))
    )
    (net (code "57") (name "unconnected-(J2-Dp1-PadA6)") (class "Default")
      (node (ref "J2") (pin "A6") (pinfunction "Dp1_A6") (pintype "bidirectional+no_connect"))
    )
    (net (code "58") (name "unconnected-(J2-Dp2-PadB6)") (class "Default")
      (node (ref "J2") (pin "B6") (pinfunction "Dp2_B6") (pintype "bidirectional+no_connect"))
    )
    (net (code "59") (name "unconnected-(J2-MNT_1-Pad1)") (class "Default")
      (node (ref "J2") (pin "1") (pinfunction "MNT_1_1") (pintype "power_in+no_connect"))
    )
    (net (code "60") (name "unconnected-(J2-MNT_2-Pad2)") (class "Default")
      (node (ref "J2") (pin "2") (pinfunction "MNT_2_2") (pintype "power_in+no_connect"))
    )
    (net (code "61") (name "unconnected-(J2-MNT_3-Pad3)") (class "Default")
      (node (ref "J2") (pin "3") (pinfunction "MNT_3_3") (pintype "power_in+no_connect"))
    )
    (net (code "62") (name "unconnected-(J2-MNT_4-Pad4)") (class "Default")
      (node (ref "J2") (pin "4") (pinfunction "MNT_4_4") (pintype "power_in+no_connect"))
    )
    (net (code "63") (name "unconnected-(J2-SBU1-PadA8)") (class "Default")
      (node (ref "J2") (pin "A8") (pinfunction "SBU1_A8") (pintype "bidirectional+no_connect"))
    )
    (net (code "64") (name "unconnected-(J2-SBU2-PadB8)") (class "Default")
      (node (ref "J2") (pin "B8") (pinfunction "SBU2_B8") (pintype "power_in+no_connect"))
    )
    (net (code "65") (name "unconnected-(J3-MNT_1-Pad1)") (class "Default")
      (node (ref "J3") (pin "1") (pinfunction "MNT_1_1") (pintype "power_in+no_connect"))
    )
    (net (code "66") (name "unconnected-(J3-MNT_2-Pad2)") (class "Default")
      (node (ref "J3") (pin "2") (pinfunction "MNT_2_2") (pintype "power_in+no_connect"))
    )
    (net (code "67") (name "unconnected-(J3-MNT_3-Pad3)") (class "Default")
      (node (ref "J3") (pin "3") (pinfunction "MNT_3_3") (pintype "power_in+no_connect"))
    )
    (net (code "68") (name "unconnected-(J3-MNT_4-Pad4)") (class "Default")
      (node (ref "J3") (pin "4") (pinfunction "MNT_4_4") (pintype "power_in+no_connect"))
    )
    (net (code "69") (name "unconnected-(J3-SBU1-PadA8)") (class "Default")
      (node (ref "J3") (pin "A8") (pinfunction "SBU1_A8") (pintype "bidirectional+no_connect"))
    )
    (net (code "70") (name "unconnected-(J3-SBU2-PadB8)") (class "Default")
      (node (ref "J3") (pin "B8") (pinfunction "SBU2_B8") (pintype "power_in+no_connect"))
    )
    (net (code "71") (name "unconnected-(J4-MNT_1-Pad1)") (class "Default")
      (node (ref "J4") (pin "1") (pinfunction "MNT_1_1") (pintype "power_in+no_connect"))
    )
    (net (code "72") (name "unconnected-(J4-MNT_2-Pad2)") (class "Default")
      (node (ref "J4") (pin "2") (pinfunction "MNT_2_2") (pintype "power_in+no_connect"))
    )
    (net (code "73") (name "unconnected-(J4-MNT_3-Pad3)") (class "Default")
      (node (ref "J4") (pin "3") (pinfunction "MNT_3_3") (pintype "power_in+no_connect"))
    )
    (net (code "74") (name "unconnected-(J4-MNT_4-Pad4)") (class "Default")
      (node (ref "J4") (pin "4") (pinfunction "MNT_4_4") (pintype "power_in+no_connect"))
    )
    (net (code "75") (name "unconnected-(J4-SBU1-PadA8)") (class "Default")
      (node (ref "J4") (pin "A8") (pinfunction "SBU1_A8") (pintype "bidirectional+no_connect"))
    )
    (net (code "76") (name "unconnected-(J4-SBU2-PadB8)") (class "Default")
      (node (ref "J4") (pin "B8") (pinfunction "SBU2_B8") (pintype "power_in+no_connect"))
    )
    (net (code "77") (name "unconnected-(J5-MNT_1-Pad1)") (class "Default")
      (node (ref "J5") (pin "1") (pinfunction "MNT_1_1") (pintype "power_in+no_connect"))
    )
    (net (code "78") (name "unconnected-(J5-MNT_2-Pad2)") (class "Default")
      (node (ref "J5") (pin "2") (pinfunction "MNT_2_2") (pintype "power_in+no_connect"))
    )
    (net (code "79") (name "unconnected-(J5-MNT_3-Pad3)") (class "Default")
      (node (ref "J5") (pin "3") (pinfunction "MNT_3_3") (pintype "power_in+no_connect"))
    )
    (net (code "80") (name "unconnected-(J5-MNT_4-Pad4)") (class "Default")
      (node (ref "J5") (pin "4") (pinfunction "MNT_4_4") (pintype "power_in+no_connect"))
    )
    (net (code "81") (name "unconnected-(J5-SBU1-PadA8)") (class "Default")
      (node (ref "J5") (pin "A8") (pinfunction "SBU1_A8") (pintype "bidirectional+no_connect"))
    )
    (net (code "82") (name "unconnected-(J5-SBU2-PadB8)") (class "Default")
      (node (ref "J5") (pin "B8") (pinfunction "SBU2_B8") (pintype "power_in+no_connect"))
    )
    (net (code "83") (name "unconnected-(J6-MNT_1-Pad1)") (class "Default")
      (node (ref "J6") (pin "1") (pinfunction "MNT_1_1") (pintype "power_in+no_connect"))
    )
    (net (code "84") (name "unconnected-(J6-MNT_2-Pad2)") (class "Default")
      (node (ref "J6") (pin "2") (pinfunction "MNT_2_2") (pintype "power_in+no_connect"))
    )
    (net (code "85") (name "unconnected-(J6-MNT_3-Pad3)") (class "Default")
      (node (ref "J6") (pin "3") (pinfunction "MNT_3_3") (pintype "power_in+no_connect"))
    )
    (net (code "86") (name "unconnected-(J6-MNT_4-Pad4)") (class "Default")
      (node (ref "J6") (pin "4") (pinfunction "MNT_4_4") (pintype "power_in+no_connect"))
    )
    (net (code "87") (name "unconnected-(J6-SBU1-PadA8)") (class "Default")
      (node (ref "J6") (pin "A8") (pinfunction "SBU1_A8") (pintype "bidirectional+no_connect"))
    )
    (net (code "88") (name "unconnected-(J6-SBU2-PadB8)") (class "Default")
      (node (ref "J6") (pin "B8") (pinfunction "SBU2_B8") (pintype "power_in+no_connect"))
    )
    (net (code "89") (name "unconnected-(J7-MH1-Pad5)") (class "Default")
      (node (ref "J7") (pin "5") (pinfunction "MH1_5") (pintype "passive+no_connect"))
    )
    (net (code "90") (name "unconnected-(J7-MH2-Pad6)") (class "Default")
      (node (ref "J7") (pin "6") (pinfunction "MH2_6") (pintype "passive+no_connect"))
    )
    (net (code "91") (name "unconnected-(J8-MH1-Pad5)") (class "Default")
      (node (ref "J8") (pin "5") (pinfunction "MH1_5") (pintype "passive+no_connect"))
    )
    (net (code "92") (name "unconnected-(J8-MH2-Pad6)") (class "Default")
      (node (ref "J8") (pin "6") (pinfunction "MH2_6") (pintype "passive+no_connect"))
    )
    (net (code "93") (name "unconnected-(J9-MH1-Pad5)") (class "Default")
      (node (ref "J9") (pin "5") (pinfunction "MH1_5") (pintype "passive+no_connect"))
    )
    (net (code "94") (name "unconnected-(J9-MH2-Pad6)") (class "Default")
      (node (ref "J9") (pin "6") (pinfunction "MH2_6") (pintype "passive+no_connect"))
    )
  )
)
